# charging_1batt.net
KiCad netlist of a schematic drawn in EAGLE
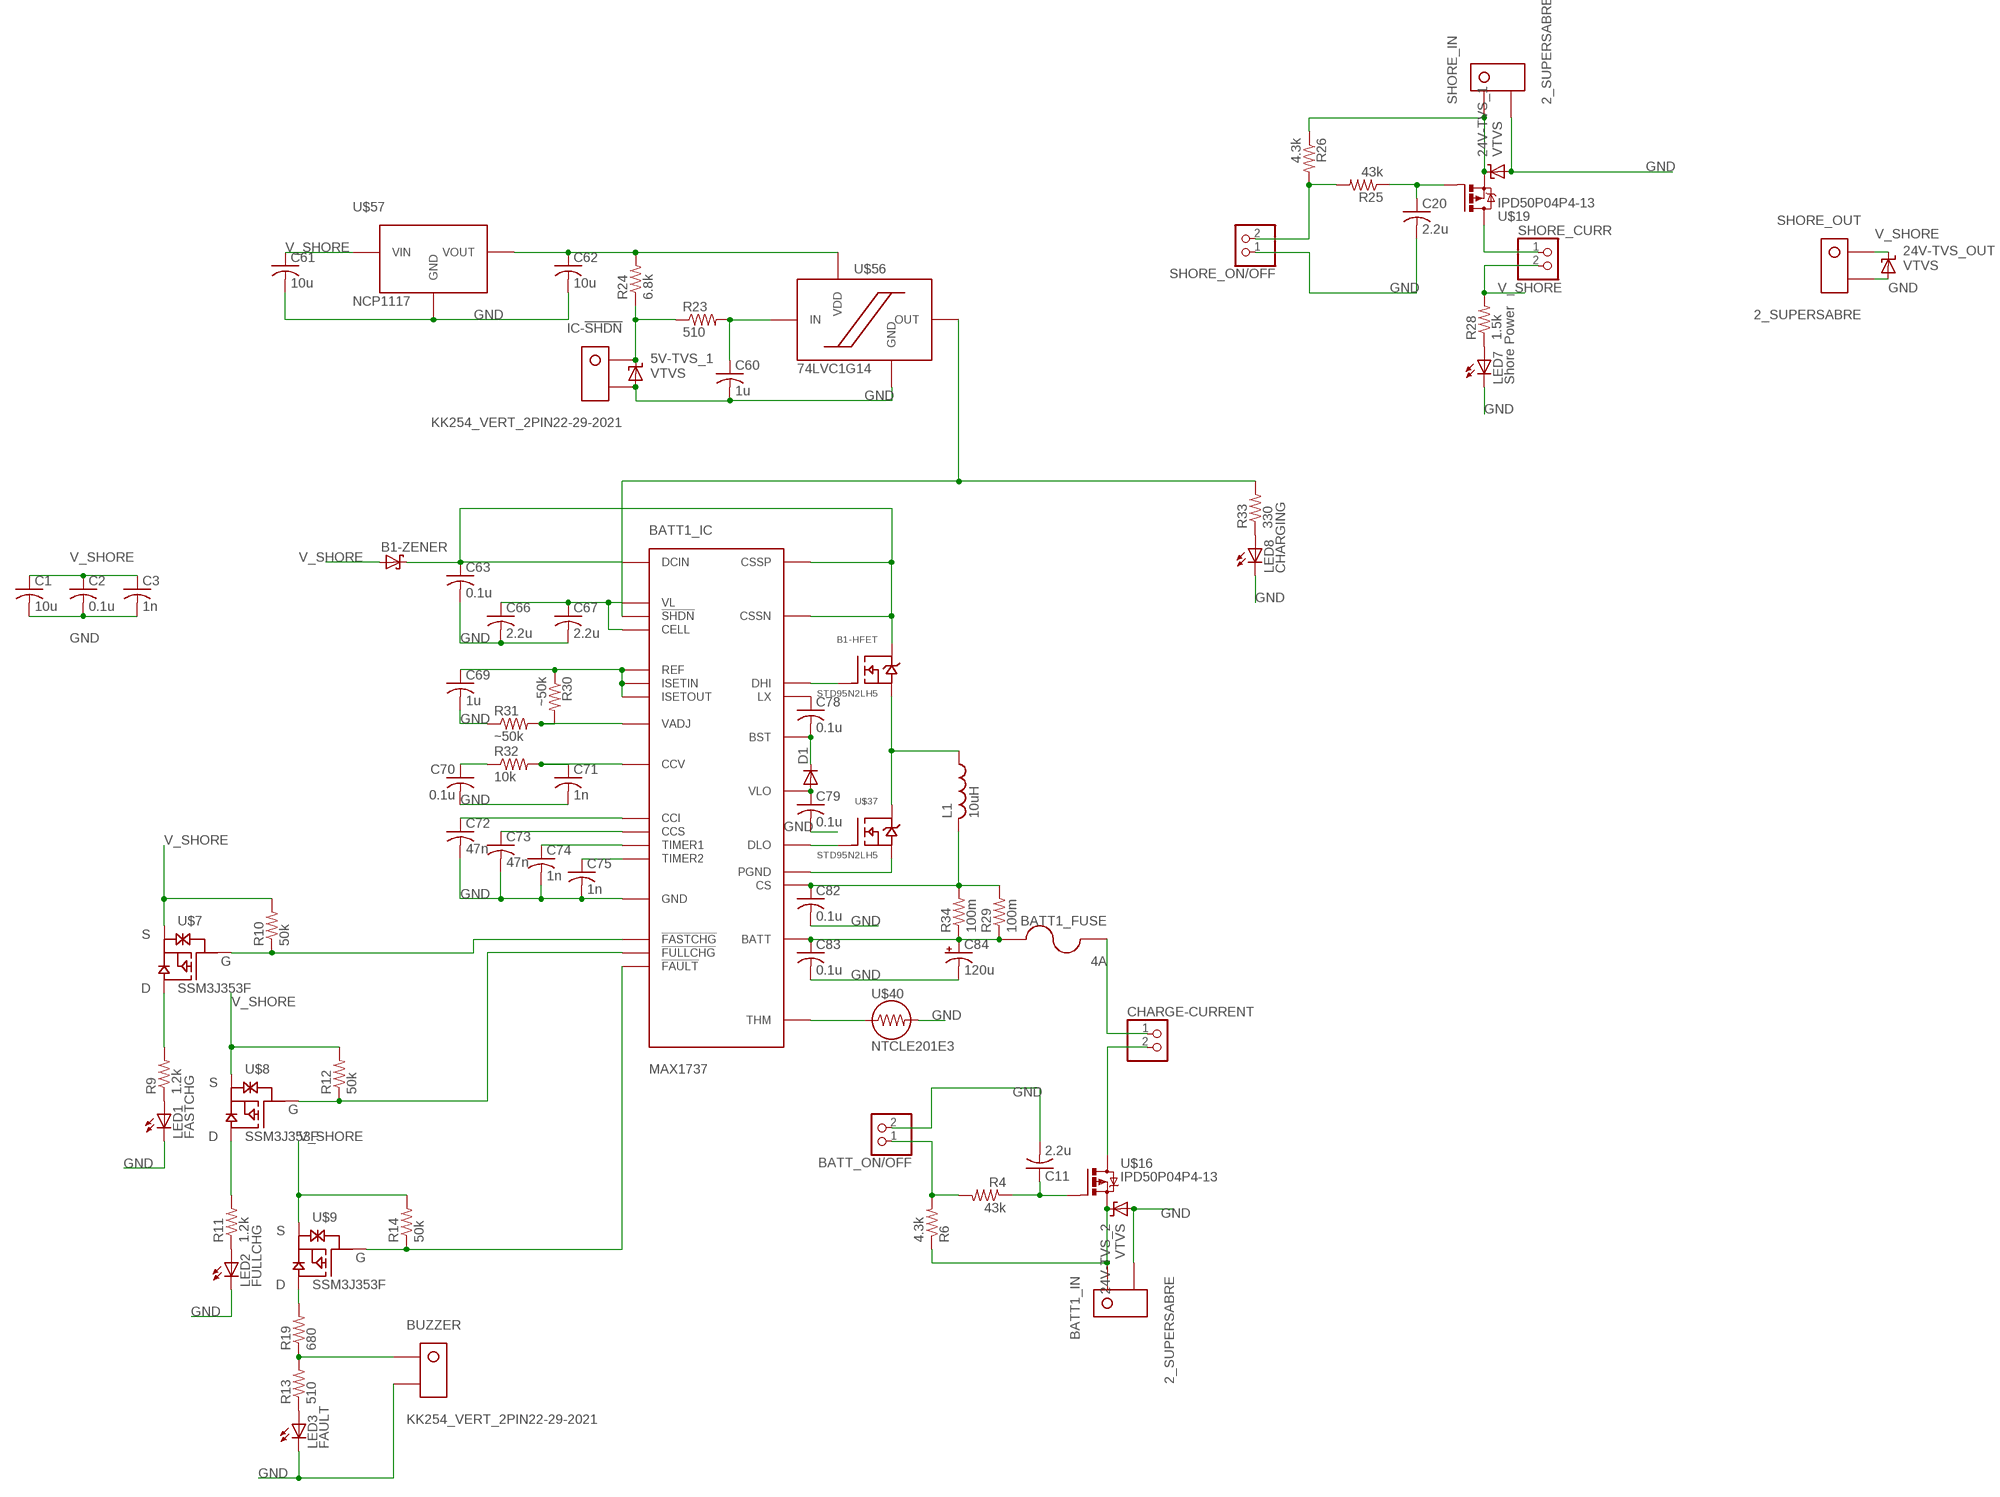
[diagram p0: schematic, sheet 1]

(export (version "E")
  (design (tool "Eeschema 10.0.6"))
  (components
    (comp (ref "5V-TVS_1")
      (value "VTVS")
      (footprint "eagle-import:DO-219AB")
      (libsource (lib "eagle-import") (part "VTVS"))
    )
    (comp (ref "24V-TVS_1")
      (value "VTVS")
      (footprint "eagle-import:DO-219AB")
      (libsource (lib "eagle-import") (part "VTVS"))
    )
    (comp (ref "24V-TVS_2")
      (value "VTVS")
      (footprint "eagle-import:DO-219AB")
      (libsource (lib "eagle-import") (part "VTVS"))
    )
    (comp (ref "24V-TVS_OUT")
      (value "VTVS")
      (footprint "eagle-import:DO-219AB")
      (libsource (lib "eagle-import") (part "VTVS"))
    )
    (comp (ref "B1-HFET")
      (value "STD95N2LH5")
      (footprint "eagle-import:DPAK")
      (libsource (lib "eagle-import") (part "STD95N2LH5"))
    )
    (comp (ref "B1-ZENER")
      (value "SCHOTTKY-DIODESOD-106")
      (footprint "eagle-import:SOD106-R")
      (libsource (lib "eagle-import") (part "SCHOTTKY-DIODESOD-106"))
    )
    (comp (ref "BATT1_FUSE")
      (value "4A")
      (footprint "eagle-import:154-OMNI-BLOK")
      (libsource (lib "eagle-import") (part "154-OMNI_BLOK"))
    )
    (comp (ref "BATT1_IC")
      (value "MAX1737")
      (footprint "eagle-import:QSOP28")
      (libsource (lib "eagle-import") (part "MAX1737"))
    )
    (comp (ref "BATT1_IN")
      (value "2_SUPERSABRE")
      (footprint "eagle-import:SUPERSABRE_2CIRCUIT")
      (libsource (lib "eagle-import") (part "2_SUPERSABRE"))
    )
    (comp (ref "BATT_ON/OFF")
      (value "PINHD-1X2")
      (footprint "eagle-import:1X02")
      (libsource (lib "eagle-import") (part "PINHD-1X2"))
    )
    (comp (ref "BUZZER")
      (value "KK254_VERT_2PIN22-29-2021")
      (footprint "eagle-import:KK254_VERT_2PIN")
      (libsource (lib "eagle-import") (part "KK254_VERT_2PIN22-29-2021"))
    )
    (comp (ref "C1")
      (value "10u")
      (footprint "eagle-import:C0805")
      (libsource (lib "eagle-import") (part "C-USC0805"))
    )
    (comp (ref "C2")
      (value "0.1u")
      (footprint "eagle-import:C0805")
      (libsource (lib "eagle-import") (part "C-USC0805"))
    )
    (comp (ref "C3")
      (value "1n")
      (footprint "eagle-import:C0805")
      (libsource (lib "eagle-import") (part "C-USC0805"))
    )
    (comp (ref "C11")
      (value "2.2u")
      (footprint "eagle-import:C0805")
      (libsource (lib "eagle-import") (part "C-USC0805"))
    )
    (comp (ref "C20")
      (value "2.2u")
      (footprint "eagle-import:C0805")
      (libsource (lib "eagle-import") (part "C-USC0805"))
    )
    (comp (ref "C60")
      (value "1u")
      (footprint "eagle-import:C0805")
      (libsource (lib "eagle-import") (part "C-USC0805"))
    )
    (comp (ref "C61")
      (value "10u")
      (footprint "eagle-import:C0805")
      (libsource (lib "eagle-import") (part "C-USC0805"))
    )
    (comp (ref "C62")
      (value "10u")
      (footprint "eagle-import:C0805")
      (libsource (lib "eagle-import") (part "C-USC0805"))
    )
    (comp (ref "C63")
      (value "0.1u")
      (footprint "eagle-import:C0805")
      (libsource (lib "eagle-import") (part "C-USC0805"))
    )
    (comp (ref "C66")
      (value "2.2u")
      (footprint "eagle-import:C0805")
      (libsource (lib "eagle-import") (part "C-USC0805"))
    )
    (comp (ref "C67")
      (value "2.2u")
      (footprint "eagle-import:C0805")
      (libsource (lib "eagle-import") (part "C-USC0805"))
    )
    (comp (ref "C69")
      (value "1u")
      (footprint "eagle-import:C0805")
      (libsource (lib "eagle-import") (part "C-USC0805"))
    )
    (comp (ref "C70")
      (value "0.1u")
      (footprint "eagle-import:C0805")
      (libsource (lib "eagle-import") (part "C-USC0805"))
    )
    (comp (ref "C71")
      (value "1n")
      (footprint "eagle-import:C0805")
      (libsource (lib "eagle-import") (part "C-USC0805"))
    )
    (comp (ref "C72")
      (value "47n")
      (footprint "eagle-import:C0805")
      (libsource (lib "eagle-import") (part "C-USC0805"))
    )
    (comp (ref "C73")
      (value "47n")
      (footprint "eagle-import:C0805")
      (libsource (lib "eagle-import") (part "C-USC0805"))
    )
    (comp (ref "C74")
      (value "1n")
      (footprint "eagle-import:C0805")
      (libsource (lib "eagle-import") (part "C-USC0805"))
    )
    (comp (ref "C75")
      (value "1n")
      (footprint "eagle-import:C0805")
      (libsource (lib "eagle-import") (part "C-USC0805"))
    )
    (comp (ref "C78")
      (value "0.1u")
      (footprint "eagle-import:C0805")
      (libsource (lib "eagle-import") (part "C-USC0805"))
    )
    (comp (ref "C79")
      (value "0.1u")
      (footprint "eagle-import:C0805")
      (libsource (lib "eagle-import") (part "C-USC0805"))
    )
    (comp (ref "C82")
      (value "0.1u")
      (footprint "eagle-import:C0805")
      (libsource (lib "eagle-import") (part "C-USC0805"))
    )
    (comp (ref "C83")
      (value "0.1u")
      (footprint "eagle-import:C0805")
      (libsource (lib "eagle-import") (part "C-USC0805"))
    )
    (comp (ref "C84")
      (value "120u")
      (footprint "eagle-import:E3,5-8")
      (libsource (lib "eagle-import") (part "CPOL-USE3.5-8"))
    )
    (comp (ref "CHARGE-CURRENT")
      (value "PINHD-1X2")
      (footprint "eagle-import:1X02")
      (libsource (lib "eagle-import") (part "PINHD-1X2"))
    )
    (comp (ref "D1")
      (value "DIODE-SOD123")
      (footprint "eagle-import:SOD123")
      (libsource (lib "eagle-import") (part "DIODE-SOD123"))
    )
    (comp (ref "IC-!SHDN!")
      (value "KK254_VERT_2PIN22-29-2021")
      (footprint "eagle-import:KK254_VERT_2PIN")
      (libsource (lib "eagle-import") (part "KK254_VERT_2PIN22-29-2021"))
    )
    (comp (ref "L1")
      (value "10uH")
      (footprint "eagle-import:L6100")
      (libsource (lib "eagle-import") (part "L-USL6100"))
    )
    (comp (ref "LED1")
      (value "FASTCHG")
      (footprint "eagle-import:CHIP-LED0805")
      (libsource (lib "eagle-import") (part "LEDCHIP-LED0805"))
    )
    (comp (ref "LED2")
      (value "FULLCHG")
      (footprint "eagle-import:CHIP-LED0805")
      (libsource (lib "eagle-import") (part "LEDCHIP-LED0805"))
    )
    (comp (ref "LED3")
      (value "FAULT")
      (footprint "eagle-import:CHIP-LED0805")
      (libsource (lib "eagle-import") (part "LEDCHIP-LED0805"))
    )
    (comp (ref "LED7")
      (value "Shore Power")
      (footprint "eagle-import:CHIP-LED0805")
      (libsource (lib "eagle-import") (part "LEDCHIP-LED0805"))
    )
    (comp (ref "LED8")
      (value "CHARGING")
      (footprint "eagle-import:CHIP-LED0805")
      (libsource (lib "eagle-import") (part "LEDCHIP-LED0805"))
    )
    (comp (ref "R4")
      (value "43k")
      (footprint "eagle-import:R0805")
      (libsource (lib "eagle-import") (part "R-US_R0805"))
    )
    (comp (ref "R6")
      (value "4.3k")
      (footprint "eagle-import:R0805")
      (libsource (lib "eagle-import") (part "R-US_R0805"))
    )
    (comp (ref "R9")
      (value "1.2k")
      (footprint "eagle-import:R0805")
      (libsource (lib "eagle-import") (part "R-US_R0805"))
    )
    (comp (ref "R10")
      (value "50k")
      (footprint "eagle-import:R0805")
      (libsource (lib "eagle-import") (part "R-US_R0805"))
    )
    (comp (ref "R11")
      (value "1.2k")
      (footprint "eagle-import:R0805")
      (libsource (lib "eagle-import") (part "R-US_R0805"))
    )
    (comp (ref "R12")
      (value "50k")
      (footprint "eagle-import:R0805")
      (libsource (lib "eagle-import") (part "R-US_R0805"))
    )
    (comp (ref "R13")
      (value "510")
      (footprint "eagle-import:R0805")
      (libsource (lib "eagle-import") (part "R-US_R0805"))
    )
    (comp (ref "R14")
      (value "50k")
      (footprint "eagle-import:R0805")
      (libsource (lib "eagle-import") (part "R-US_R0805"))
    )
    (comp (ref "R19")
      (value "680")
      (footprint "eagle-import:R0805")
      (libsource (lib "eagle-import") (part "R-US_R0805"))
    )
    (comp (ref "R23")
      (value "510")
      (footprint "eagle-import:R0805")
      (libsource (lib "eagle-import") (part "R-US_R0805"))
    )
    (comp (ref "R24")
      (value "6.8k")
      (footprint "eagle-import:R0805")
      (libsource (lib "eagle-import") (part "R-US_R0805"))
    )
    (comp (ref "R25")
      (value "43k")
      (footprint "eagle-import:R0805")
      (libsource (lib "eagle-import") (part "R-US_R0805"))
    )
    (comp (ref "R26")
      (value "4.3k")
      (footprint "eagle-import:R0805")
      (libsource (lib "eagle-import") (part "R-US_R0805"))
    )
    (comp (ref "R28")
      (value "1.5k")
      (footprint "eagle-import:R0805")
      (libsource (lib "eagle-import") (part "R-US_R0805"))
    )
    (comp (ref "R29")
      (value "100m")
      (footprint "eagle-import:R2512")
      (libsource (lib "eagle-import") (part "R-US_R2512"))
    )
    (comp (ref "R30")
      (value "~50k")
      (footprint "eagle-import:R0805")
      (libsource (lib "eagle-import") (part "R-US_R0805"))
    )
    (comp (ref "R31")
      (value "~50k")
      (footprint "eagle-import:R0805")
      (libsource (lib "eagle-import") (part "R-US_R0805"))
    )
    (comp (ref "R32")
      (value "10k")
      (footprint "eagle-import:R0805")
      (libsource (lib "eagle-import") (part "R-US_R0805"))
    )
    (comp (ref "R33")
      (value "330")
      (footprint "eagle-import:R0805")
      (libsource (lib "eagle-import") (part "R-US_R0805"))
    )
    (comp (ref "R34")
      (value "100m")
      (footprint "eagle-import:R2512")
      (libsource (lib "eagle-import") (part "R-US_R2512"))
    )
    (comp (ref "SHORE_CURR")
      (value "PINHD-1X2")
      (footprint "eagle-import:1X02")
      (libsource (lib "eagle-import") (part "PINHD-1X2"))
    )
    (comp (ref "SHORE_IN")
      (value "2_SUPERSABRE")
      (footprint "eagle-import:SUPERSABRE_2CIRCUIT")
      (libsource (lib "eagle-import") (part "2_SUPERSABRE"))
    )
    (comp (ref "SHORE_ON/OFF")
      (value "PINHD-1X2")
      (footprint "eagle-import:1X02")
      (libsource (lib "eagle-import") (part "PINHD-1X2"))
    )
    (comp (ref "SHORE_OUT")
      (value "2_SUPERSABRE")
      (footprint "eagle-import:SUPERSABRE_2CIRCUIT")
      (libsource (lib "eagle-import") (part "2_SUPERSABRE"))
    )
    (comp (ref "U$7")
      (value "SSM3J353F")
      (footprint "eagle-import:SOT-346-3_S-MINI")
      (libsource (lib "eagle-import") (part "SSM3J353F"))
    )
    (comp (ref "U$8")
      (value "SSM3J353F")
      (footprint "eagle-import:SOT-346-3_S-MINI")
      (libsource (lib "eagle-import") (part "SSM3J353F"))
    )
    (comp (ref "U$9")
      (value "SSM3J353F")
      (footprint "eagle-import:SOT-346-3_S-MINI")
      (libsource (lib "eagle-import") (part "SSM3J353F"))
    )
    (comp (ref "U$16")
      (value "IPD50P04P4-13")
      (footprint "eagle-import:TO252-3")
      (libsource (lib "eagle-import") (part "IPD50P04P4-13"))
    )
    (comp (ref "U$19")
      (value "IPD50P04P4-13")
      (footprint "eagle-import:TO252-3")
      (libsource (lib "eagle-import") (part "IPD50P04P4-13"))
    )
    (comp (ref "U$37")
      (value "STD95N2LH5")
      (footprint "eagle-import:DPAK")
      (libsource (lib "eagle-import") (part "STD95N2LH5"))
    )
    (comp (ref "U$40")
      (value "NTCLE201E3")
      (footprint "eagle-import:2-0.3MM-LEADS")
      (libsource (lib "eagle-import") (part "NTCLE201E3"))
    )
    (comp (ref "U$56")
      (value "74LVC1G14")
      (footprint "eagle-import:TSSOP5")
      (libsource (lib "eagle-import") (part "74LVC1G14"))
    )
    (comp (ref "U$57")
      (value "NCP1117")
      (footprint "eagle-import:SOT-223")
      (libsource (lib "eagle-import") (part "NCP1117"))
    )
  )
  (nets
    (net (code "1") (name "/GND") (class "Default")
      (node (ref "24V-TVS_1") (pin "P$1") (pinfunction "A_P$1") (pintype "passive"))
      (node (ref "24V-TVS_2") (pin "P$1") (pinfunction "A_P$1") (pintype "passive"))
      (node (ref "24V-TVS_OUT") (pin "P$1") (pinfunction "A_P$1") (pintype "passive"))
      (node (ref "5V-TVS_1") (pin "P$1") (pinfunction "A_P$1") (pintype "passive"))
      (node (ref "BATT1_IC") (pin "6") (pinfunction "GND_6") (pintype "bidirectional"))
      (node (ref "BATT1_IN") (pin "P$2") (pinfunction "P$2_P$2") (pintype "bidirectional"))
      (node (ref "BATT_ON/OFF") (pin "2") (pinfunction "2_2") (pintype "passive"))
      (node (ref "BUZZER") (pin "P$2") (pinfunction "P$2_P$2") (pintype "bidirectional"))
      (node (ref "C1") (pin "2") (pinfunction "2_2") (pintype "passive"))
      (node (ref "C11") (pin "2") (pinfunction "2_2") (pintype "passive"))
      (node (ref "C2") (pin "2") (pinfunction "2_2") (pintype "passive"))
      (node (ref "C20") (pin "2") (pinfunction "2_2") (pintype "passive"))
      (node (ref "C3") (pin "2") (pinfunction "2_2") (pintype "passive"))
      (node (ref "C60") (pin "2") (pinfunction "2_2") (pintype "passive"))
      (node (ref "C61") (pin "2") (pinfunction "2_2") (pintype "passive"))
      (node (ref "C62") (pin "2") (pinfunction "2_2") (pintype "passive"))
      (node (ref "C63") (pin "2") (pinfunction "2_2") (pintype "passive"))
      (node (ref "C66") (pin "2") (pinfunction "2_2") (pintype "passive"))
      (node (ref "C67") (pin "2") (pinfunction "2_2") (pintype "passive"))
      (node (ref "C69") (pin "2") (pinfunction "2_2") (pintype "passive"))
      (node (ref "C70") (pin "2") (pinfunction "2_2") (pintype "passive"))
      (node (ref "C71") (pin "2") (pinfunction "2_2") (pintype "passive"))
      (node (ref "C72") (pin "2") (pinfunction "2_2") (pintype "passive"))
      (node (ref "C73") (pin "2") (pinfunction "2_2") (pintype "passive"))
      (node (ref "C74") (pin "2") (pinfunction "2_2") (pintype "passive"))
      (node (ref "C75") (pin "2") (pinfunction "2_2") (pintype "passive"))
      (node (ref "C79") (pin "2") (pinfunction "2_2") (pintype "passive"))
      (node (ref "C82") (pin "2") (pinfunction "2_2") (pintype "passive"))
      (node (ref "C83") (pin "2") (pinfunction "2_2") (pintype "passive"))
      (node (ref "C84") (pin "-") (pinfunction "-_-") (pintype "passive"))
      (node (ref "IC-!SHDN!") (pin "P$2") (pinfunction "P$2_P$2") (pintype "bidirectional"))
      (node (ref "LED1") (pin "C") (pinfunction "C_C") (pintype "passive"))
      (node (ref "LED2") (pin "C") (pinfunction "C_C") (pintype "passive"))
      (node (ref "LED3") (pin "C") (pinfunction "C_C") (pintype "passive"))
      (node (ref "LED7") (pin "C") (pinfunction "C_C") (pintype "passive"))
      (node (ref "LED8") (pin "C") (pinfunction "C_C") (pintype "passive"))
      (node (ref "R31") (pin "1") (pinfunction "1_1") (pintype "passive"))
      (node (ref "SHORE_IN") (pin "P$2") (pinfunction "P$2_P$2") (pintype "bidirectional"))
      (node (ref "SHORE_ON/OFF") (pin "1") (pinfunction "1_1") (pintype "passive"))
      (node (ref "SHORE_OUT") (pin "P$2") (pinfunction "P$2_P$2") (pintype "bidirectional"))
      (node (ref "U$40") (pin "P$2") (pinfunction "2_P$2") (pintype "passive"))
      (node (ref "U$56") (pin "P$3") (pinfunction "GND_P$3") (pintype "bidirectional"))
      (node (ref "U$57") (pin "P$1") (pinfunction "GND_P$1") (pintype "bidirectional"))
    )
    (net (code "2") (name "/V_SHORE") (class "Default")
      (node (ref "24V-TVS_OUT") (pin "P$2") (pinfunction "C_P$2") (pintype "passive"))
      (node (ref "B1-ZENER") (pin "A") (pinfunction "A_A") (pintype "passive"))
      (node (ref "C1") (pin "1") (pinfunction "1_1") (pintype "passive"))
      (node (ref "C2") (pin "1") (pinfunction "1_1") (pintype "passive"))
      (node (ref "C3") (pin "1") (pinfunction "1_1") (pintype "passive"))
      (node (ref "C61") (pin "1") (pinfunction "1_1") (pintype "passive"))
      (node (ref "R10") (pin "2") (pinfunction "2_2") (pintype "passive"))
      (node (ref "R12") (pin "2") (pinfunction "2_2") (pintype "passive"))
      (node (ref "R14") (pin "2") (pinfunction "2_2") (pintype "passive"))
      (node (ref "R28") (pin "2") (pinfunction "2_2") (pintype "passive"))
      (node (ref "SHORE_CURR") (pin "2") (pinfunction "2_2") (pintype "passive"))
      (node (ref "SHORE_OUT") (pin "P$1") (pinfunction "P$1_P$1") (pintype "bidirectional"))
      (node (ref "U$57") (pin "P$3") (pinfunction "VIN_P$3") (pintype "bidirectional"))
      (node (ref "U$7") (pin "P$3") (pinfunction "S_P$3") (pintype "bidirectional"))
      (node (ref "U$8") (pin "P$3") (pinfunction "S_P$3") (pintype "bidirectional"))
      (node (ref "U$9") (pin "P$3") (pinfunction "S_P$3") (pintype "bidirectional"))
    )
    (net (code "3") (name "Net-(5V-TVS_1-C)") (class "Default")
      (node (ref "5V-TVS_1") (pin "P$2") (pinfunction "C_P$2") (pintype "passive"))
      (node (ref "IC-!SHDN!") (pin "P$1") (pinfunction "P$1_P$1") (pintype "bidirectional"))
      (node (ref "R23") (pin "1") (pinfunction "1_1") (pintype "passive"))
      (node (ref "R24") (pin "1") (pinfunction "1_1") (pintype "passive"))
    )
    (net (code "4") (name "Net-(24V-TVS_1-C)") (class "Default")
      (node (ref "24V-TVS_1") (pin "P$2") (pinfunction "C_P$2") (pintype "passive"))
      (node (ref "R26") (pin "1") (pinfunction "1_1") (pintype "passive"))
      (node (ref "SHORE_IN") (pin "P$1") (pinfunction "P$1_P$1") (pintype "bidirectional"))
      (node (ref "U$19") (pin "TAB") (pinfunction "D_TAB") (pintype "passive"))
    )
    (net (code "5") (name "Net-(24V-TVS_2-C)") (class "Default")
      (node (ref "24V-TVS_2") (pin "P$2") (pinfunction "C_P$2") (pintype "passive"))
      (node (ref "BATT1_IN") (pin "P$1") (pinfunction "P$1_P$1") (pintype "bidirectional"))
      (node (ref "R6") (pin "1") (pinfunction "1_1") (pintype "passive"))
      (node (ref "U$16") (pin "TAB") (pinfunction "D_TAB") (pintype "passive"))
    )
    (net (code "6") (name "Net-(B1-HFET-D)") (class "Default")
      (node (ref "B1-HFET") (pin "TAB") (pinfunction "D_TAB") (pintype "bidirectional"))
      (node (ref "B1-ZENER") (pin "C") (pinfunction "C_C") (pintype "passive"))
      (node (ref "BATT1_IC") (pin "26") (pinfunction "CSSN_26") (pintype "bidirectional"))
      (node (ref "BATT1_IC") (pin "27") (pinfunction "CSSP_27") (pintype "bidirectional"))
      (node (ref "BATT1_IC") (pin "28") (pinfunction "DCIN_28") (pintype "bidirectional"))
      (node (ref "C63") (pin "1") (pinfunction "1_1") (pintype "passive"))
    )
    (net (code "7") (name "Net-(B1-HFET-G)") (class "Default")
      (node (ref "B1-HFET") (pin "1") (pinfunction "G_1") (pintype "bidirectional"))
      (node (ref "BATT1_IC") (pin "25") (pinfunction "DHI_25") (pintype "bidirectional"))
    )
    (net (code "8") (name "Net-(B1-HFET-S)") (class "Default")
      (node (ref "B1-HFET") (pin "3") (pinfunction "S_3") (pintype "bidirectional"))
      (node (ref "L1") (pin "P$1") (pinfunction "1_P$1") (pintype "passive"))
      (node (ref "U$37") (pin "TAB") (pinfunction "D_TAB") (pintype "bidirectional"))
    )
    (net (code "9") (name "Net-(BATT1_FUSE-PadP$1)") (class "Default")
      (node (ref "BATT1_FUSE") (pin "P$1") (pinfunction "P$1_P$1") (pintype "bidirectional"))
      (node (ref "CHARGE-CURRENT") (pin "1") (pinfunction "1_1") (pintype "passive"))
    )
    (net (code "10") (name "Net-(BATT1_IC-BATT)") (class "Default")
      (node (ref "BATT1_FUSE") (pin "P$2") (pinfunction "P$2_P$2") (pintype "bidirectional"))
      (node (ref "BATT1_IC") (pin "7") (pinfunction "BATT_7") (pintype "bidirectional"))
      (node (ref "C83") (pin "1") (pinfunction "1_1") (pintype "passive"))
      (node (ref "C84") (pin "+") (pinfunction "+_+") (pintype "passive"))
      (node (ref "R29") (pin "1") (pinfunction "1_1") (pintype "passive"))
      (node (ref "R34") (pin "1") (pinfunction "1_1") (pintype "passive"))
    )
    (net (code "11") (name "Net-(BATT1_IC-BST)") (class "Default")
      (node (ref "BATT1_IC") (pin "23") (pinfunction "BST_23") (pintype "bidirectional"))
      (node (ref "C78") (pin "2") (pinfunction "2_2") (pintype "passive"))
      (node (ref "D1") (pin "C") (pinfunction "C_C") (pintype "passive"))
    )
    (net (code "12") (name "Net-(BATT1_IC-CCI)") (class "Default")
      (node (ref "BATT1_IC") (pin "11") (pinfunction "CCI_11") (pintype "bidirectional"))
      (node (ref "C72") (pin "1") (pinfunction "1_1") (pintype "passive"))
    )
    (net (code "13") (name "Net-(BATT1_IC-CCS)") (class "Default")
      (node (ref "BATT1_IC") (pin "10") (pinfunction "CCS_10") (pintype "bidirectional"))
      (node (ref "C73") (pin "1") (pinfunction "1_1") (pintype "passive"))
    )
    (net (code "14") (name "Net-(BATT1_IC-CCV)") (class "Default")
      (node (ref "BATT1_IC") (pin "9") (pinfunction "CCV_9") (pintype "bidirectional"))
      (node (ref "C71") (pin "1") (pinfunction "1_1") (pintype "passive"))
      (node (ref "R32") (pin "2") (pinfunction "2_2") (pintype "passive"))
    )
    (net (code "15") (name "Net-(BATT1_IC-CELL)") (class "Default")
      (node (ref "BATT1_IC") (pin "1") (pinfunction "VL_1") (pintype "bidirectional"))
      (node (ref "BATT1_IC") (pin "12") (pinfunction "CELL_12") (pintype "bidirectional"))
      (node (ref "C66") (pin "1") (pinfunction "1_1") (pintype "passive"))
      (node (ref "C67") (pin "1") (pinfunction "1_1") (pintype "passive"))
    )
    (net (code "16") (name "Net-(BATT1_IC-CS)") (class "Default")
      (node (ref "BATT1_IC") (pin "19") (pinfunction "CS_19") (pintype "bidirectional"))
      (node (ref "C82") (pin "1") (pinfunction "1_1") (pintype "passive"))
      (node (ref "L1") (pin "P$2") (pinfunction "2_P$2") (pintype "passive"))
      (node (ref "R29") (pin "2") (pinfunction "2_2") (pintype "passive"))
      (node (ref "R34") (pin "2") (pinfunction "2_2") (pintype "passive"))
    )
    (net (code "17") (name "Net-(BATT1_IC-DLO)") (class "Default")
      (node (ref "BATT1_IC") (pin "21") (pinfunction "DLO_21") (pintype "bidirectional"))
      (node (ref "U$37") (pin "1") (pinfunction "G_1") (pintype "bidirectional"))
    )
    (net (code "18") (name "Net-(BATT1_IC-ISETIN)") (class "Default")
      (node (ref "BATT1_IC") (pin "2") (pinfunction "ISETIN_2") (pintype "bidirectional"))
      (node (ref "BATT1_IC") (pin "3") (pinfunction "ISETOUT_3") (pintype "bidirectional"))
      (node (ref "BATT1_IC") (pin "5") (pinfunction "REF_5") (pintype "bidirectional"))
      (node (ref "C69") (pin "1") (pinfunction "1_1") (pintype "passive"))
      (node (ref "R30") (pin "1") (pinfunction "1_1") (pintype "passive"))
    )
    (net (code "19") (name "Net-(BATT1_IC-LX)") (class "Default")
      (node (ref "BATT1_IC") (pin "24") (pinfunction "LX_24") (pintype "bidirectional"))
      (node (ref "C78") (pin "1") (pinfunction "1_1") (pintype "passive"))
    )
    (net (code "20") (name "Net-(BATT1_IC-PGND)") (class "Default")
      (node (ref "BATT1_IC") (pin "20") (pinfunction "PGND_20") (pintype "bidirectional"))
      (node (ref "U$37") (pin "3") (pinfunction "S_3") (pintype "bidirectional"))
    )
    (net (code "21") (name "Net-(BATT1_IC-THM)") (class "Default")
      (node (ref "BATT1_IC") (pin "4") (pinfunction "THM_4") (pintype "bidirectional"))
      (node (ref "U$40") (pin "P$1") (pinfunction "1_P$1") (pintype "passive"))
    )
    (net (code "22") (name "Net-(BATT1_IC-TIMER1)") (class "Default")
      (node (ref "BATT1_IC") (pin "13") (pinfunction "TIMER1_13") (pintype "bidirectional"))
      (node (ref "C74") (pin "1") (pinfunction "1_1") (pintype "passive"))
    )
    (net (code "23") (name "Net-(BATT1_IC-TIMER2)") (class "Default")
      (node (ref "BATT1_IC") (pin "14") (pinfunction "TIMER2_14") (pintype "bidirectional"))
      (node (ref "C75") (pin "1") (pinfunction "1_1") (pintype "passive"))
    )
    (net (code "24") (name "Net-(BATT1_IC-VADJ)") (class "Default")
      (node (ref "BATT1_IC") (pin "8") (pinfunction "VADJ_8") (pintype "bidirectional"))
      (node (ref "R30") (pin "2") (pinfunction "2_2") (pintype "passive"))
      (node (ref "R31") (pin "2") (pinfunction "2_2") (pintype "passive"))
    )
    (net (code "25") (name "Net-(BATT1_IC-VLO)") (class "Default")
      (node (ref "BATT1_IC") (pin "22") (pinfunction "VLO_22") (pintype "bidirectional"))
      (node (ref "C79") (pin "1") (pinfunction "1_1") (pintype "passive"))
      (node (ref "D1") (pin "A") (pinfunction "A_A") (pintype "passive"))
    )
    (net (code "26") (name "Net-(BATT1_IC-~{FASTCHG})") (class "Default")
      (node (ref "BATT1_IC") (pin "16") (pinfunction "~{FASTCHG}_16") (pintype "bidirectional"))
      (node (ref "R10") (pin "1") (pinfunction "1_1") (pintype "passive"))
      (node (ref "U$7") (pin "P$1") (pinfunction "G_P$1") (pintype "bidirectional"))
    )
    (net (code "27") (name "Net-(BATT1_IC-~{FAULT})") (class "Default")
      (node (ref "BATT1_IC") (pin "15") (pinfunction "~{FAULT}_15") (pintype "bidirectional"))
      (node (ref "R14") (pin "1") (pinfunction "1_1") (pintype "passive"))
      (node (ref "U$9") (pin "P$1") (pinfunction "G_P$1") (pintype "bidirectional"))
    )
    (net (code "28") (name "Net-(BATT1_IC-~{FULLCHG})") (class "Default")
      (node (ref "BATT1_IC") (pin "17") (pinfunction "~{FULLCHG}_17") (pintype "bidirectional"))
      (node (ref "R12") (pin "1") (pinfunction "1_1") (pintype "passive"))
      (node (ref "U$8") (pin "P$1") (pinfunction "G_P$1") (pintype "bidirectional"))
    )
    (net (code "29") (name "Net-(BATT1_IC-~{SHDN})") (class "Default")
      (node (ref "BATT1_IC") (pin "18") (pinfunction "~{SHDN}_18") (pintype "bidirectional"))
      (node (ref "R33") (pin "2") (pinfunction "2_2") (pintype "passive"))
      (node (ref "U$56") (pin "P$4") (pinfunction "OUT_P$4") (pintype "bidirectional"))
    )
    (net (code "30") (name "Net-(BATT_ON/OFF-Pad1)") (class "Default")
      (node (ref "BATT_ON/OFF") (pin "1") (pinfunction "1_1") (pintype "passive"))
      (node (ref "R4") (pin "2") (pinfunction "2_2") (pintype "passive"))
      (node (ref "R6") (pin "2") (pinfunction "2_2") (pintype "passive"))
    )
    (net (code "31") (name "Net-(BUZZER-PadP$1)") (class "Default")
      (node (ref "BUZZER") (pin "P$1") (pinfunction "P$1_P$1") (pintype "bidirectional"))
      (node (ref "R13") (pin "2") (pinfunction "2_2") (pintype "passive"))
      (node (ref "R19") (pin "1") (pinfunction "1_1") (pintype "passive"))
    )
    (net (code "32") (name "Net-(C70-Pad1)") (class "Default")
      (node (ref "C70") (pin "1") (pinfunction "1_1") (pintype "passive"))
      (node (ref "R32") (pin "1") (pinfunction "1_1") (pintype "passive"))
    )
    (net (code "33") (name "Net-(LED1-PadA)") (class "Default")
      (node (ref "LED1") (pin "A") (pinfunction "A_A") (pintype "passive"))
      (node (ref "R9") (pin "1") (pinfunction "1_1") (pintype "passive"))
    )
    (net (code "34") (name "Net-(LED2-PadA)") (class "Default")
      (node (ref "LED2") (pin "A") (pinfunction "A_A") (pintype "passive"))
      (node (ref "R11") (pin "1") (pinfunction "1_1") (pintype "passive"))
    )
    (net (code "35") (name "Net-(LED3-PadA)") (class "Default")
      (node (ref "LED3") (pin "A") (pinfunction "A_A") (pintype "passive"))
      (node (ref "R13") (pin "1") (pinfunction "1_1") (pintype "passive"))
    )
    (net (code "36") (name "Net-(LED7-PadA)") (class "Default")
      (node (ref "LED7") (pin "A") (pinfunction "A_A") (pintype "passive"))
      (node (ref "R28") (pin "1") (pinfunction "1_1") (pintype "passive"))
    )
    (net (code "37") (name "Net-(LED8-PadA)") (class "Default")
      (node (ref "LED8") (pin "A") (pinfunction "A_A") (pintype "passive"))
      (node (ref "R33") (pin "1") (pinfunction "1_1") (pintype "passive"))
    )
    (net (code "38") (name "Net-(R25-Pad2)") (class "Default")
      (node (ref "R25") (pin "2") (pinfunction "2_2") (pintype "passive"))
      (node (ref "R26") (pin "2") (pinfunction "2_2") (pintype "passive"))
      (node (ref "SHORE_ON/OFF") (pin "2") (pinfunction "2_2") (pintype "passive"))
    )
    (net (code "39") (name "Net-(U$7-D)") (class "Default")
      (node (ref "R9") (pin "2") (pinfunction "2_2") (pintype "passive"))
      (node (ref "U$7") (pin "P$2") (pinfunction "D_P$2") (pintype "bidirectional"))
    )
    (net (code "40") (name "Net-(U$8-D)") (class "Default")
      (node (ref "R11") (pin "2") (pinfunction "2_2") (pintype "passive"))
      (node (ref "U$8") (pin "P$2") (pinfunction "D_P$2") (pintype "bidirectional"))
    )
    (net (code "41") (name "Net-(U$9-D)") (class "Default")
      (node (ref "R19") (pin "2") (pinfunction "2_2") (pintype "passive"))
      (node (ref "U$9") (pin "P$2") (pinfunction "D_P$2") (pintype "bidirectional"))
    )
    (net (code "42") (name "Net-(U$16-G)") (class "Default")
      (node (ref "C11") (pin "1") (pinfunction "1_1") (pintype "passive"))
      (node (ref "R4") (pin "1") (pinfunction "1_1") (pintype "passive"))
      (node (ref "U$16") (pin "1") (pinfunction "G_1") (pintype "passive"))
    )
    (net (code "43") (name "Net-(U$16-S)") (class "Default")
      (node (ref "CHARGE-CURRENT") (pin "2") (pinfunction "2_2") (pintype "passive"))
      (node (ref "U$16") (pin "3") (pinfunction "S_3") (pintype "passive"))
    )
    (net (code "44") (name "Net-(U$19-G)") (class "Default")
      (node (ref "C20") (pin "1") (pinfunction "1_1") (pintype "passive"))
      (node (ref "R25") (pin "1") (pinfunction "1_1") (pintype "passive"))
      (node (ref "U$19") (pin "1") (pinfunction "G_1") (pintype "passive"))
    )
    (net (code "45") (name "Net-(U$19-S)") (class "Default")
      (node (ref "SHORE_CURR") (pin "1") (pinfunction "1_1") (pintype "passive"))
      (node (ref "U$19") (pin "3") (pinfunction "S_3") (pintype "passive"))
    )
    (net (code "46") (name "Net-(U$56-IN)") (class "Default")
      (node (ref "C60") (pin "1") (pinfunction "1_1") (pintype "passive"))
      (node (ref "R23") (pin "2") (pinfunction "2_2") (pintype "passive"))
      (node (ref "U$56") (pin "P$2") (pinfunction "IN_P$2") (pintype "bidirectional"))
    )
    (net (code "47") (name "Net-(U$56-VDD)") (class "Default")
      (node (ref "C62") (pin "1") (pinfunction "1_1") (pintype "passive"))
      (node (ref "R24") (pin "2") (pinfunction "2_2") (pintype "passive"))
      (node (ref "U$56") (pin "P$5") (pinfunction "VDD_P$5") (pintype "bidirectional"))
      (node (ref "U$57") (pin "P$2") (pinfunction "VOUT_P$2") (pintype "bidirectional"))
      (node (ref "U$57") (pin "P$4") (pinfunction "VOUT_P$4") (pintype "bidirectional"))
    )
  )
)
